# auxboxshield1_58.net
KiCad netlist of a schematic drawn in EAGLE
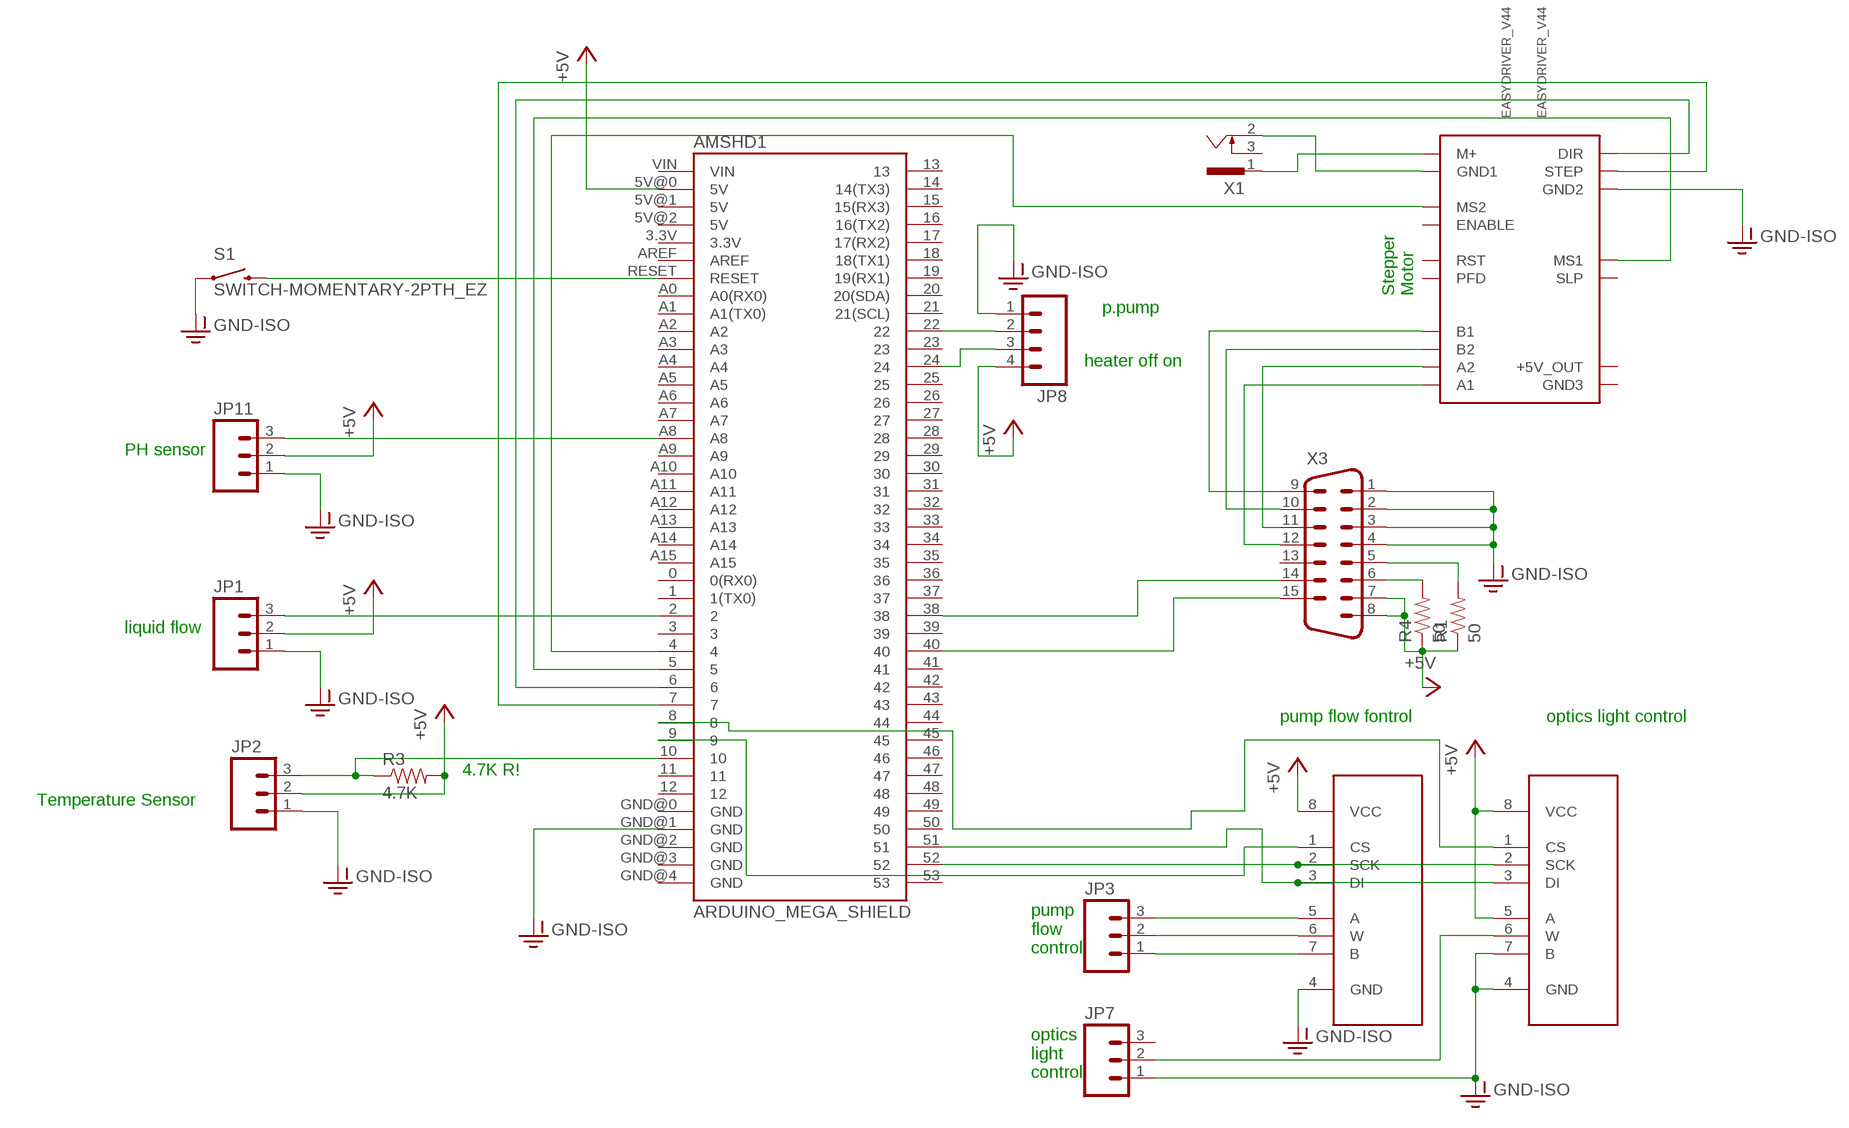
[diagram p0: schematic, sheet 1]

(export (version "E")
  (design (tool "Eeschema 10.0.6"))
  (components
    (comp (ref "AMSHD1")
      (value "ARDUINO_MEGA_SHIELD")
      (footprint "eagle-import:ARDUINO_MEGA_SHIELD")
      (libsource (lib "eagle-import") (part "ARDUINO_MEGA_SHIELD"))
    )
    (comp (ref "EASYDRIVER_V44")
      (value "EASYDRIVER_V44")
      (footprint "eagle-import:EASYDRIVER_V44")
      (libsource (lib "eagle-import") (part "EASYDRIVER_V44"))
    )
    (comp (ref "JP1")
      (value "M03POLAR")
      (footprint "eagle-import:MOLEX-1X3")
      (libsource (lib "eagle-import") (part "M03POLAR"))
    )
    (comp (ref "JP2")
      (value "M03POLAR")
      (footprint "eagle-import:MOLEX-1X3")
      (libsource (lib "eagle-import") (part "M03POLAR"))
    )
    (comp (ref "JP3")
      (value "M03POLAR")
      (footprint "eagle-import:MOLEX-1X3")
      (libsource (lib "eagle-import") (part "M03POLAR"))
    )
    (comp (ref "JP7")
      (value "M03POLAR")
      (footprint "eagle-import:MOLEX-1X3")
      (libsource (lib "eagle-import") (part "M03POLAR"))
    )
    (comp (ref "JP8")
      (value "M04POLAR")
      (footprint "eagle-import:MOLEX-1X4")
      (libsource (lib "eagle-import") (part "M04POLAR"))
    )
    (comp (ref "JP11")
      (value "M03POLAR")
      (footprint "eagle-import:MOLEX-1X3")
      (libsource (lib "eagle-import") (part "M03POLAR"))
    )
    (comp (ref "R1")
      (value "50")
      (footprint "eagle-import:AXIAL-0.3")
      (libsource (lib "eagle-import") (part "10OHM-1/4W-5%(PTH)"))
    )
    (comp (ref "R3")
      (value "4.7K")
      (footprint "eagle-import:AXIAL-0.3")
      (libsource (lib "eagle-import") (part "10OHM-1/4W-5%(PTH)"))
    )
    (comp (ref "R4")
      (value "50")
      (footprint "eagle-import:AXIAL-0.3")
      (libsource (lib "eagle-import") (part "10OHM-1/4W-5%(PTH)"))
    )
    (comp (ref "S1")
      (value "SWITCH-MOMENTARY-2PTH_EZ")
      (footprint "eagle-import:TACTILE-PTH-EZ")
      (libsource (lib "eagle-import") (part "SWITCH-MOMENTARY-2PTH_EZ"))
    )
    (comp (ref "U1")
      (value "MCP41XXXDIL")
      (footprint "eagle-import:DIL-08")
      (libsource (lib "eagle-import") (part "MCP41XXXDIL"))
    )
    (comp (ref "U2")
      (value "MCP41XXXDIL")
      (footprint "eagle-import:DIL-08")
      (libsource (lib "eagle-import") (part "MCP41XXXDIL"))
    )
    (comp (ref "X1")
      (value "SCD-014A")
      (footprint "eagle-import:SCD-014-A")
      (libsource (lib "eagle-import") (part "SCD-014A"))
    )
    (comp (ref "X3")
      (value "M15V")
      (footprint "eagle-import:M15V")
      (libsource (lib "eagle-import") (part "M15V"))
    )
  )
  (nets
    (net (code "1") (name "+5V") (class "Default")
      (node (ref "AMSHD1") (pin "5V@0") (pinfunction "5V_5V@0") (pintype "bidirectional"))
      (node (ref "JP1") (pin "2") (pinfunction "2_2") (pintype "passive"))
      (node (ref "JP11") (pin "2") (pinfunction "2_2") (pintype "passive"))
      (node (ref "JP2") (pin "2") (pinfunction "2_2") (pintype "passive"))
      (node (ref "JP8") (pin "4") (pinfunction "4_4") (pintype "passive"))
      (node (ref "R1") (pin "P$1") (pinfunction "1_P$1") (pintype "passive"))
      (node (ref "R3") (pin "P$2") (pinfunction "2_P$2") (pintype "passive"))
      (node (ref "R4") (pin "P$1") (pinfunction "1_P$1") (pintype "passive"))
      (node (ref "U1") (pin "5") (pinfunction "A_5") (pintype "bidirectional"))
      (node (ref "U1") (pin "8") (pinfunction "VCC_8") (pintype "bidirectional"))
      (node (ref "U2") (pin "8") (pinfunction "VCC_8") (pintype "bidirectional"))
      (node (ref "X3") (pin "7") (pinfunction "7_7") (pintype "passive"))
      (node (ref "X3") (pin "8") (pinfunction "8_8") (pintype "passive"))
    )
    (net (code "2") (name "GND-ISO") (class "Default")
      (node (ref "AMSHD1") (pin "GND@1") (pinfunction "GND_GND@1") (pintype "bidirectional"))
      (node (ref "EASYDRIVER_V44") (pin "GND2") (pinfunction "GND2_GND2") (pintype "bidirectional"))
      (node (ref "JP1") (pin "1") (pinfunction "1_1") (pintype "passive"))
      (node (ref "JP11") (pin "1") (pinfunction "1_1") (pintype "passive"))
      (node (ref "JP2") (pin "1") (pinfunction "1_1") (pintype "passive"))
      (node (ref "JP7") (pin "1") (pinfunction "1_1") (pintype "passive"))
      (node (ref "JP8") (pin "1") (pinfunction "1_1") (pintype "passive"))
      (node (ref "S1") (pin "1") (pinfunction "1_1") (pintype "passive"))
      (node (ref "U1") (pin "4") (pinfunction "GND_4") (pintype "bidirectional"))
      (node (ref "U1") (pin "7") (pinfunction "B_7") (pintype "bidirectional"))
      (node (ref "U2") (pin "4") (pinfunction "GND_4") (pintype "bidirectional"))
      (node (ref "X3") (pin "1") (pinfunction "1_1") (pintype "passive"))
      (node (ref "X3") (pin "2") (pinfunction "2_2") (pintype "passive"))
      (node (ref "X3") (pin "3") (pinfunction "3_3") (pintype "passive"))
      (node (ref "X3") (pin "4") (pinfunction "4_4") (pintype "passive"))
    )
    (net (code "3") (name "Net-(AMSHD1-Pad2)") (class "Default")
      (node (ref "AMSHD1") (pin "2") (pinfunction "2_2") (pintype "bidirectional"))
      (node (ref "JP1") (pin "3") (pinfunction "3_3") (pintype "passive"))
    )
    (net (code "4") (name "Net-(AMSHD1-Pad4)") (class "Default")
      (node (ref "AMSHD1") (pin "4") (pinfunction "4_4") (pintype "bidirectional"))
      (node (ref "EASYDRIVER_V44") (pin "MS2") (pinfunction "MS2_MS2") (pintype "bidirectional"))
    )
    (net (code "5") (name "Net-(AMSHD1-Pad5)") (class "Default")
      (node (ref "AMSHD1") (pin "5") (pinfunction "5_5") (pintype "bidirectional"))
      (node (ref "EASYDRIVER_V44") (pin "MS1") (pinfunction "MS1_MS1") (pintype "bidirectional"))
    )
    (net (code "6") (name "Net-(AMSHD1-Pad6)") (class "Default")
      (node (ref "AMSHD1") (pin "6") (pinfunction "6_6") (pintype "bidirectional"))
      (node (ref "EASYDRIVER_V44") (pin "DIR") (pinfunction "DIR_DIR") (pintype "bidirectional"))
    )
    (net (code "7") (name "Net-(AMSHD1-Pad7)") (class "Default")
      (node (ref "AMSHD1") (pin "7") (pinfunction "7_7") (pintype "bidirectional"))
      (node (ref "EASYDRIVER_V44") (pin "STEP") (pinfunction "STEP_STEP") (pintype "bidirectional"))
    )
    (net (code "8") (name "Net-(AMSHD1-Pad22)") (class "Default")
      (node (ref "AMSHD1") (pin "22") (pinfunction "22_22") (pintype "bidirectional"))
      (node (ref "JP8") (pin "2") (pinfunction "2_2") (pintype "passive"))
    )
    (net (code "9") (name "Net-(AMSHD1-Pad24)") (class "Default")
      (node (ref "AMSHD1") (pin "24") (pinfunction "24_24") (pintype "bidirectional"))
      (node (ref "JP8") (pin "3") (pinfunction "3_3") (pintype "passive"))
    )
    (net (code "10") (name "Net-(AMSHD1-Pad38)") (class "Default")
      (node (ref "AMSHD1") (pin "38") (pinfunction "38_38") (pintype "bidirectional"))
      (node (ref "X3") (pin "14") (pinfunction "14_14") (pintype "passive"))
    )
    (net (code "11") (name "Net-(AMSHD1-Pad40)") (class "Default")
      (node (ref "AMSHD1") (pin "40") (pinfunction "40_40") (pintype "bidirectional"))
      (node (ref "X3") (pin "15") (pinfunction "15_15") (pintype "passive"))
    )
    (net (code "12") (name "Net-(AMSHD1-PadA8)") (class "Default")
      (node (ref "AMSHD1") (pin "A8") (pinfunction "A8_A8") (pintype "bidirectional"))
      (node (ref "JP11") (pin "3") (pinfunction "3_3") (pintype "passive"))
    )
    (net (code "13") (name "Net-(EASYDRIVER_V44-PadA1)") (class "Default")
      (node (ref "EASYDRIVER_V44") (pin "A1") (pinfunction "A1_A1") (pintype "bidirectional"))
      (node (ref "X3") (pin "12") (pinfunction "12_12") (pintype "passive"))
    )
    (net (code "14") (name "Net-(EASYDRIVER_V44-PadA2)") (class "Default")
      (node (ref "EASYDRIVER_V44") (pin "A2") (pinfunction "A2_A2") (pintype "bidirectional"))
      (node (ref "X3") (pin "11") (pinfunction "11_11") (pintype "passive"))
    )
    (net (code "15") (name "Net-(EASYDRIVER_V44-PadB1)") (class "Default")
      (node (ref "EASYDRIVER_V44") (pin "B1") (pinfunction "B1_B1") (pintype "bidirectional"))
      (node (ref "X3") (pin "9") (pinfunction "9_9") (pintype "passive"))
    )
    (net (code "16") (name "Net-(EASYDRIVER_V44-PadB2)") (class "Default")
      (node (ref "EASYDRIVER_V44") (pin "B2") (pinfunction "B2_B2") (pintype "bidirectional"))
      (node (ref "X3") (pin "10") (pinfunction "10_10") (pintype "passive"))
    )
    (net (code "17") (name "Net-(EASYDRIVER_V44-PadGND1)") (class "Default")
      (node (ref "EASYDRIVER_V44") (pin "GND1") (pinfunction "GND1_GND1") (pintype "bidirectional"))
      (node (ref "X1") (pin "2") (pinfunction "2_2") (pintype "passive"))
    )
    (net (code "18") (name "Net-(EASYDRIVER_V44-PadM+)") (class "Default")
      (node (ref "EASYDRIVER_V44") (pin "M+") (pinfunction "M+_M+") (pintype "bidirectional"))
      (node (ref "X1") (pin "1") (pinfunction "1_1") (pintype "passive"))
    )
    (net (code "19") (name "Net-(R1-2)") (class "Default")
      (node (ref "R1") (pin "P$2") (pinfunction "2_P$2") (pintype "passive"))
      (node (ref "X3") (pin "5") (pinfunction "5_5") (pintype "passive"))
    )
    (net (code "20") (name "Net-(R3-1)") (class "Default")
      (node (ref "AMSHD1") (pin "10") (pinfunction "10_10") (pintype "bidirectional"))
      (node (ref "JP2") (pin "3") (pinfunction "3_3") (pintype "passive"))
      (node (ref "R3") (pin "P$1") (pinfunction "1_P$1") (pintype "passive"))
    )
    (net (code "21") (name "Net-(R4-2)") (class "Default")
      (node (ref "R4") (pin "P$2") (pinfunction "2_P$2") (pintype "passive"))
      (node (ref "X3") (pin "6") (pinfunction "6_6") (pintype "passive"))
    )
    (net (code "22") (name "Net-(S1-2)") (class "Default")
      (node (ref "AMSHD1") (pin "RESET") (pinfunction "RESET_RESET") (pintype "bidirectional"))
      (node (ref "S1") (pin "3") (pinfunction "2_3") (pintype "passive"))
    )
    (net (code "23") (name "Net-(U1-CS)") (class "Default")
      (node (ref "AMSHD1") (pin "8") (pinfunction "8_8") (pintype "bidirectional"))
      (node (ref "U1") (pin "1") (pinfunction "CS_1") (pintype "bidirectional"))
    )
    (net (code "24") (name "Net-(U1-DI)") (class "Default")
      (node (ref "AMSHD1") (pin "51") (pinfunction "51_51") (pintype "bidirectional"))
      (node (ref "U1") (pin "3") (pinfunction "DI_3") (pintype "bidirectional"))
      (node (ref "U2") (pin "3") (pinfunction "DI_3") (pintype "bidirectional"))
    )
    (net (code "25") (name "Net-(U1-SCK)") (class "Default")
      (node (ref "AMSHD1") (pin "52") (pinfunction "52_52") (pintype "bidirectional"))
      (node (ref "U1") (pin "2") (pinfunction "SCK_2") (pintype "bidirectional"))
      (node (ref "U2") (pin "2") (pinfunction "SCK_2") (pintype "bidirectional"))
    )
    (net (code "26") (name "Net-(U1-W)") (class "Default")
      (node (ref "JP7") (pin "2") (pinfunction "2_2") (pintype "passive"))
      (node (ref "U1") (pin "6") (pinfunction "W_6") (pintype "bidirectional"))
    )
    (net (code "27") (name "Net-(U2-A)") (class "Default")
      (node (ref "JP3") (pin "3") (pinfunction "3_3") (pintype "passive"))
      (node (ref "U2") (pin "5") (pinfunction "A_5") (pintype "bidirectional"))
    )
    (net (code "28") (name "Net-(U2-B)") (class "Default")
      (node (ref "JP3") (pin "1") (pinfunction "1_1") (pintype "passive"))
      (node (ref "U2") (pin "7") (pinfunction "B_7") (pintype "bidirectional"))
    )
    (net (code "29") (name "Net-(U2-CS)") (class "Default")
      (node (ref "AMSHD1") (pin "9") (pinfunction "9_9") (pintype "bidirectional"))
      (node (ref "U2") (pin "1") (pinfunction "CS_1") (pintype "bidirectional"))
    )
    (net (code "30") (name "Net-(U2-W)") (class "Default")
      (node (ref "JP3") (pin "2") (pinfunction "2_2") (pintype "passive"))
      (node (ref "U2") (pin "6") (pinfunction "W_6") (pintype "bidirectional"))
    )
    (net (code "31") (name "unconnected-(AMSHD1-0(RX0)-Pad0)") (class "Default")
      (node (ref "AMSHD1") (pin "0") (pinfunction "0(RX0)_0") (pintype "bidirectional"))
    )
    (net (code "32") (name "unconnected-(AMSHD1-1(TX0)-Pad1)") (class "Default")
      (node (ref "AMSHD1") (pin "1") (pinfunction "1(TX0)_1") (pintype "bidirectional"))
    )
    (net (code "33") (name "unconnected-(AMSHD1-5V-Pad5V@1)") (class "Default")
      (node (ref "AMSHD1") (pin "5V@1") (pinfunction "5V_5V@1") (pintype "bidirectional"))
    )
    (net (code "34") (name "unconnected-(AMSHD1-5V-Pad5V@2)") (class "Default")
      (node (ref "AMSHD1") (pin "5V@2") (pinfunction "5V_5V@2") (pintype "bidirectional"))
    )
    (net (code "35") (name "unconnected-(AMSHD1-14(TX3)-Pad14)") (class "Default")
      (node (ref "AMSHD1") (pin "14") (pinfunction "14(TX3)_14") (pintype "bidirectional"))
    )
    (net (code "36") (name "unconnected-(AMSHD1-15(RX3)-Pad15)") (class "Default")
      (node (ref "AMSHD1") (pin "15") (pinfunction "15(RX3)_15") (pintype "bidirectional"))
    )
    (net (code "37") (name "unconnected-(AMSHD1-16(TX2)-Pad16)") (class "Default")
      (node (ref "AMSHD1") (pin "16") (pinfunction "16(TX2)_16") (pintype "bidirectional"))
    )
    (net (code "38") (name "unconnected-(AMSHD1-17(RX2)-Pad17)") (class "Default")
      (node (ref "AMSHD1") (pin "17") (pinfunction "17(RX2)_17") (pintype "bidirectional"))
    )
    (net (code "39") (name "unconnected-(AMSHD1-18(TX1)-Pad18)") (class "Default")
      (node (ref "AMSHD1") (pin "18") (pinfunction "18(TX1)_18") (pintype "bidirectional"))
    )
    (net (code "40") (name "unconnected-(AMSHD1-19(RX1)-Pad19)") (class "Default")
      (node (ref "AMSHD1") (pin "19") (pinfunction "19(RX1)_19") (pintype "bidirectional"))
    )
    (net (code "41") (name "unconnected-(AMSHD1-20(SDA)-Pad20)") (class "Default")
      (node (ref "AMSHD1") (pin "20") (pinfunction "20(SDA)_20") (pintype "bidirectional"))
    )
    (net (code "42") (name "unconnected-(AMSHD1-21(SCL)-Pad21)") (class "Default")
      (node (ref "AMSHD1") (pin "21") (pinfunction "21(SCL)_21") (pintype "bidirectional"))
    )
    (net (code "43") (name "unconnected-(AMSHD1-A0(RX0)-PadA0)") (class "Default")
      (node (ref "AMSHD1") (pin "A0") (pinfunction "A0(RX0)_A0") (pintype "bidirectional"))
    )
    (net (code "44") (name "unconnected-(AMSHD1-A1(TX0)-PadA1)") (class "Default")
      (node (ref "AMSHD1") (pin "A1") (pinfunction "A1(TX0)_A1") (pintype "bidirectional"))
    )
    (net (code "45") (name "unconnected-(AMSHD1-GND-PadGND@0)") (class "Default")
      (node (ref "AMSHD1") (pin "GND@0") (pinfunction "GND_GND@0") (pintype "bidirectional"))
    )
    (net (code "46") (name "unconnected-(AMSHD1-GND-PadGND@2)") (class "Default")
      (node (ref "AMSHD1") (pin "GND@2") (pinfunction "GND_GND@2") (pintype "bidirectional"))
    )
    (net (code "47") (name "unconnected-(AMSHD1-GND-PadGND@3)") (class "Default")
      (node (ref "AMSHD1") (pin "GND@3") (pinfunction "GND_GND@3") (pintype "bidirectional"))
    )
    (net (code "48") (name "unconnected-(AMSHD1-GND-PadGND@4)") (class "Default")
      (node (ref "AMSHD1") (pin "GND@4") (pinfunction "GND_GND@4") (pintype "bidirectional"))
    )
    (net (code "49") (name "unconnected-(AMSHD1-Pad3)") (class "Default")
      (node (ref "AMSHD1") (pin "3") (pinfunction "3_3") (pintype "bidirectional"))
    )
    (net (code "50") (name "unconnected-(AMSHD1-Pad3.3V)") (class "Default")
      (node (ref "AMSHD1") (pin "3.3V") (pinfunction "3.3V_3.3V") (pintype "bidirectional"))
    )
    (net (code "51") (name "unconnected-(AMSHD1-Pad11)") (class "Default")
      (node (ref "AMSHD1") (pin "11") (pinfunction "11_11") (pintype "bidirectional"))
    )
    (net (code "52") (name "unconnected-(AMSHD1-Pad12)") (class "Default")
      (node (ref "AMSHD1") (pin "12") (pinfunction "12_12") (pintype "bidirectional"))
    )
    (net (code "53") (name "unconnected-(AMSHD1-Pad13)") (class "Default")
      (node (ref "AMSHD1") (pin "13") (pinfunction "13_13") (pintype "bidirectional"))
    )
    (net (code "54") (name "unconnected-(AMSHD1-Pad23)") (class "Default")
      (node (ref "AMSHD1") (pin "23") (pinfunction "23_23") (pintype "bidirectional"))
    )
    (net (code "55") (name "unconnected-(AMSHD1-Pad25)") (class "Default")
      (node (ref "AMSHD1") (pin "25") (pinfunction "25_25") (pintype "bidirectional"))
    )
    (net (code "56") (name "unconnected-(AMSHD1-Pad26)") (class "Default")
      (node (ref "AMSHD1") (pin "26") (pinfunction "26_26") (pintype "bidirectional"))
    )
    (net (code "57") (name "unconnected-(AMSHD1-Pad27)") (class "Default")
      (node (ref "AMSHD1") (pin "27") (pinfunction "27_27") (pintype "bidirectional"))
    )
    (net (code "58") (name "unconnected-(AMSHD1-Pad28)") (class "Default")
      (node (ref "AMSHD1") (pin "28") (pinfunction "28_28") (pintype "bidirectional"))
    )
    (net (code "59") (name "unconnected-(AMSHD1-Pad29)") (class "Default")
      (node (ref "AMSHD1") (pin "29") (pinfunction "29_29") (pintype "bidirectional"))
    )
    (net (code "60") (name "unconnected-(AMSHD1-Pad30)") (class "Default")
      (node (ref "AMSHD1") (pin "30") (pinfunction "30_30") (pintype "bidirectional"))
    )
    (net (code "61") (name "unconnected-(AMSHD1-Pad31)") (class "Default")
      (node (ref "AMSHD1") (pin "31") (pinfunction "31_31") (pintype "bidirectional"))
    )
    (net (code "62") (name "unconnected-(AMSHD1-Pad32)") (class "Default")
      (node (ref "AMSHD1") (pin "32") (pinfunction "32_32") (pintype "bidirectional"))
    )
    (net (code "63") (name "unconnected-(AMSHD1-Pad33)") (class "Default")
      (node (ref "AMSHD1") (pin "33") (pinfunction "33_33") (pintype "bidirectional"))
    )
    (net (code "64") (name "unconnected-(AMSHD1-Pad34)") (class "Default")
      (node (ref "AMSHD1") (pin "34") (pinfunction "34_34") (pintype "bidirectional"))
    )
    (net (code "65") (name "unconnected-(AMSHD1-Pad35)") (class "Default")
      (node (ref "AMSHD1") (pin "35") (pinfunction "35_35") (pintype "bidirectional"))
    )
    (net (code "66") (name "unconnected-(AMSHD1-Pad36)") (class "Default")
      (node (ref "AMSHD1") (pin "36") (pinfunction "36_36") (pintype "bidirectional"))
    )
    (net (code "67") (name "unconnected-(AMSHD1-Pad37)") (class "Default")
      (node (ref "AMSHD1") (pin "37") (pinfunction "37_37") (pintype "bidirectional"))
    )
    (net (code "68") (name "unconnected-(AMSHD1-Pad39)") (class "Default")
      (node (ref "AMSHD1") (pin "39") (pinfunction "39_39") (pintype "bidirectional"))
    )
    (net (code "69") (name "unconnected-(AMSHD1-Pad41)") (class "Default")
      (node (ref "AMSHD1") (pin "41") (pinfunction "41_41") (pintype "bidirectional"))
    )
    (net (code "70") (name "unconnected-(AMSHD1-Pad42)") (class "Default")
      (node (ref "AMSHD1") (pin "42") (pinfunction "42_42") (pintype "bidirectional"))
    )
    (net (code "71") (name "unconnected-(AMSHD1-Pad43)") (class "Default")
      (node (ref "AMSHD1") (pin "43") (pinfunction "43_43") (pintype "bidirectional"))
    )
    (net (code "72") (name "unconnected-(AMSHD1-Pad44)") (class "Default")
      (node (ref "AMSHD1") (pin "44") (pinfunction "44_44") (pintype "bidirectional"))
    )
    (net (code "73") (name "unconnected-(AMSHD1-Pad45)") (class "Default")
      (node (ref "AMSHD1") (pin "45") (pinfunction "45_45") (pintype "bidirectional"))
    )
    (net (code "74") (name "unconnected-(AMSHD1-Pad46)") (class "Default")
      (node (ref "AMSHD1") (pin "46") (pinfunction "46_46") (pintype "bidirectional"))
    )
    (net (code "75") (name "unconnected-(AMSHD1-Pad47)") (class "Default")
      (node (ref "AMSHD1") (pin "47") (pinfunction "47_47") (pintype "bidirectional"))
    )
    (net (code "76") (name "unconnected-(AMSHD1-Pad48)") (class "Default")
      (node (ref "AMSHD1") (pin "48") (pinfunction "48_48") (pintype "bidirectional"))
    )
    (net (code "77") (name "unconnected-(AMSHD1-Pad49)") (class "Default")
      (node (ref "AMSHD1") (pin "49") (pinfunction "49_49") (pintype "bidirectional"))
    )
    (net (code "78") (name "unconnected-(AMSHD1-Pad50)") (class "Default")
      (node (ref "AMSHD1") (pin "50") (pinfunction "50_50") (pintype "bidirectional"))
    )
    (net (code "79") (name "unconnected-(AMSHD1-Pad53)") (class "Default")
      (node (ref "AMSHD1") (pin "53") (pinfunction "53_53") (pintype "bidirectional"))
    )
    (net (code "80") (name "unconnected-(AMSHD1-PadA2)") (class "Default")
      (node (ref "AMSHD1") (pin "A2") (pinfunction "A2_A2") (pintype "bidirectional"))
    )
    (net (code "81") (name "unconnected-(AMSHD1-PadA3)") (class "Default")
      (node (ref "AMSHD1") (pin "A3") (pinfunction "A3_A3") (pintype "bidirectional"))
    )
    (net (code "82") (name "unconnected-(AMSHD1-PadA4)") (class "Default")
      (node (ref "AMSHD1") (pin "A4") (pinfunction "A4_A4") (pintype "bidirectional"))
    )
    (net (code "83") (name "unconnected-(AMSHD1-PadA5)") (class "Default")
      (node (ref "AMSHD1") (pin "A5") (pinfunction "A5_A5") (pintype "bidirectional"))
    )
    (net (code "84") (name "unconnected-(AMSHD1-PadA6)") (class "Default")
      (node (ref "AMSHD1") (pin "A6") (pinfunction "A6_A6") (pintype "bidirectional"))
    )
    (net (code "85") (name "unconnected-(AMSHD1-PadA7)") (class "Default")
      (node (ref "AMSHD1") (pin "A7") (pinfunction "A7_A7") (pintype "bidirectional"))
    )
    (net (code "86") (name "unconnected-(AMSHD1-PadA9)") (class "Default")
      (node (ref "AMSHD1") (pin "A9") (pinfunction "A9_A9") (pintype "bidirectional"))
    )
    (net (code "87") (name "unconnected-(AMSHD1-PadA10)") (class "Default")
      (node (ref "AMSHD1") (pin "A10") (pinfunction "A10_A10") (pintype "bidirectional"))
    )
    (net (code "88") (name "unconnected-(AMSHD1-PadA11)") (class "Default")
      (node (ref "AMSHD1") (pin "A11") (pinfunction "A11_A11") (pintype "bidirectional"))
    )
    (net (code "89") (name "unconnected-(AMSHD1-PadA12)") (class "Default")
      (node (ref "AMSHD1") (pin "A12") (pinfunction "A12_A12") (pintype "bidirectional"))
    )
    (net (code "90") (name "unconnected-(AMSHD1-PadA13)") (class "Default")
      (node (ref "AMSHD1") (pin "A13") (pinfunction "A13_A13") (pintype "bidirectional"))
    )
    (net (code "91") (name "unconnected-(AMSHD1-PadA14)") (class "Default")
      (node (ref "AMSHD1") (pin "A14") (pinfunction "A14_A14") (pintype "bidirectional"))
    )
    (net (code "92") (name "unconnected-(AMSHD1-PadA15)") (class "Default")
      (node (ref "AMSHD1") (pin "A15") (pinfunction "A15_A15") (pintype "bidirectional"))
    )
    (net (code "93") (name "unconnected-(AMSHD1-PadAREF)") (class "Default")
      (node (ref "AMSHD1") (pin "AREF") (pinfunction "AREF_AREF") (pintype "bidirectional"))
    )
    (net (code "94") (name "unconnected-(AMSHD1-PadVIN)") (class "Default")
      (node (ref "AMSHD1") (pin "VIN") (pinfunction "VIN_VIN") (pintype "bidirectional"))
    )
    (net (code "95") (name "unconnected-(EASYDRIVER_V44-+5V_OUT-PadP$11)") (class "Default")
      (node (ref "EASYDRIVER_V44") (pin "P$11") (pinfunction "+5V_OUT_P$11") (pintype "bidirectional"))
    )
    (net (code "96") (name "unconnected-(EASYDRIVER_V44-PadENABLE)") (class "Default")
      (node (ref "EASYDRIVER_V44") (pin "ENABLE") (pinfunction "ENABLE_ENABLE") (pintype "bidirectional"))
    )
    (net (code "97") (name "unconnected-(EASYDRIVER_V44-PadGND3)") (class "Default")
      (node (ref "EASYDRIVER_V44") (pin "GND3") (pinfunction "GND3_GND3") (pintype "bidirectional"))
    )
    (net (code "98") (name "unconnected-(EASYDRIVER_V44-PadPFD)") (class "Default")
      (node (ref "EASYDRIVER_V44") (pin "PFD") (pinfunction "PFD_PFD") (pintype "bidirectional"))
    )
    (net (code "99") (name "unconnected-(EASYDRIVER_V44-PadRST)") (class "Default")
      (node (ref "EASYDRIVER_V44") (pin "RST") (pinfunction "RST_RST") (pintype "bidirectional"))
    )
    (net (code "100") (name "unconnected-(EASYDRIVER_V44-SLP-PadSLEEP)") (class "Default")
      (node (ref "EASYDRIVER_V44") (pin "SLEEP") (pinfunction "SLP_SLEEP") (pintype "bidirectional"))
    )
    (net (code "101") (name "unconnected-(JP7-Pad3)") (class "Default")
      (node (ref "JP7") (pin "3") (pinfunction "3_3") (pintype "passive"))
    )
    (net (code "102") (name "unconnected-(X1-Pad3)") (class "Default")
      (node (ref "X1") (pin "3") (pinfunction "3_3") (pintype "passive"))
    )
    (net (code "103") (name "unconnected-(X3-Pad13)") (class "Default")
      (node (ref "X3") (pin "13") (pinfunction "13_13") (pintype "passive"))
    )
  )
)
